# fpga-bank3.net
KiCad netlist of a schematic drawn in Altium Designer
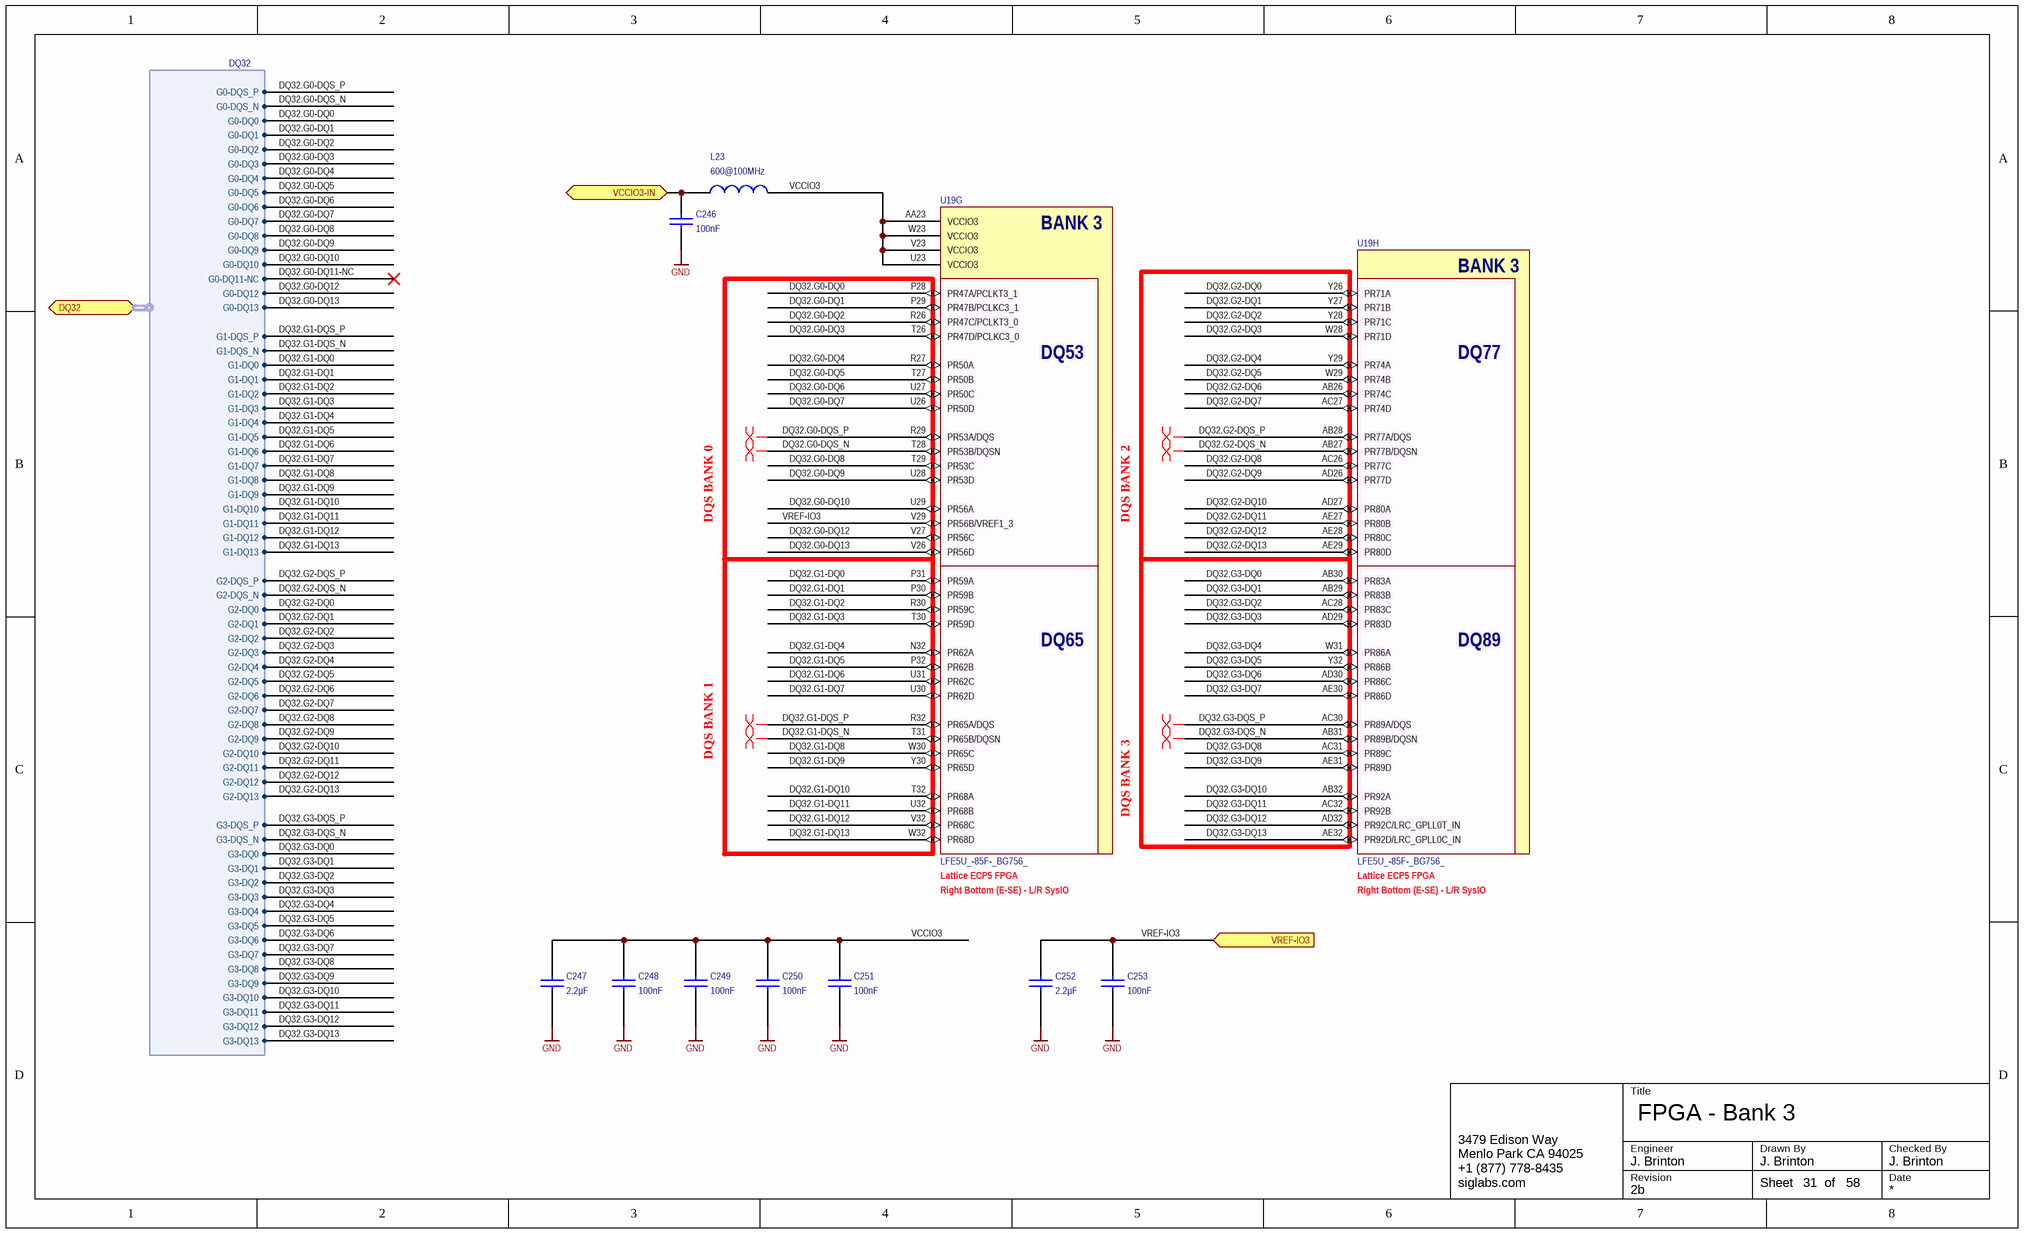
[diagram p0: fpga-bank3.SchDoc]

(export (version "E")
  (design (tool "Eeschema 10.0.6"))
  (components
    (comp (ref "C246")
      (value "100nF")
      (footprint "generic:CAPC1005X56N")
      (description "Ceramic Capacitor 100nF ±10% 16V X7R 0402")
      (fields (field (name "MANUFACTURER") "Murata") (field (name "TOLERANCE") "±10%"))
      (libsource (lib "murata") (part "GRM155R71A104KA01J"))
    )
    (comp (ref "C247")
      (value "2.2µF")
      (footprint "generic:CAPC1608X90N")
      (description "Ceramic Capacitor 2.2uF ±10% 10V X7R 0603")
      (fields (field (name "MANUFACTURER") "Murata") (field (name "TOLERANCE") "±10%"))
      (libsource (lib "murata") (part "GRM188R71A225KE15D"))
    )
    (comp (ref "C248")
      (value "100nF")
      (footprint "generic:CAPC1005X56N")
      (description "Ceramic Capacitor 100nF ±10% 16V X7R 0402")
      (fields (field (name "MANUFACTURER") "Murata") (field (name "TOLERANCE") "±10%"))
      (libsource (lib "murata") (part "GRM155R71A104KA01J"))
    )
    (comp (ref "C249")
      (value "100nF")
      (footprint "generic:CAPC1005X56N")
      (description "Ceramic Capacitor 100nF ±10% 16V X7R 0402")
      (fields (field (name "MANUFACTURER") "Murata") (field (name "TOLERANCE") "±10%"))
      (libsource (lib "murata") (part "GRM155R71A104KA01J"))
    )
    (comp (ref "C250")
      (value "100nF")
      (footprint "generic:CAPC1005X56N")
      (description "Ceramic Capacitor 100nF ±10% 16V X7R 0402")
      (fields (field (name "MANUFACTURER") "Murata") (field (name "TOLERANCE") "±10%"))
      (libsource (lib "murata") (part "GRM155R71A104KA01J"))
    )
    (comp (ref "C251")
      (value "100nF")
      (footprint "generic:CAPC1005X56N")
      (description "Ceramic Capacitor 100nF ±10% 16V X7R 0402")
      (fields (field (name "MANUFACTURER") "Murata") (field (name "TOLERANCE") "±10%"))
      (libsource (lib "murata") (part "GRM155R71A104KA01J"))
    )
    (comp (ref "C252")
      (value "2.2µF")
      (footprint "generic:CAPC1608X90N")
      (description "Ceramic Capacitor 2.2uF ±10% 10V X7R 0603")
      (fields (field (name "MANUFACTURER") "Murata") (field (name "TOLERANCE") "±10%"))
      (libsource (lib "murata") (part "GRM188R71A225KE15D"))
    )
    (comp (ref "C253")
      (value "100nF")
      (footprint "generic:CAPC1005X56N")
      (description "Ceramic Capacitor 100nF ±10% 16V X7R 0402")
      (fields (field (name "MANUFACTURER") "Murata") (field (name "TOLERANCE") "±10%"))
      (libsource (lib "murata") (part "GRM155R71A104KA01J"))
    )
    (comp (ref "L23")
      (value "600@100MHz")
      (footprint "0402")
      (description "Ferrite Bead 600-Ohm @ 100MHz 900mA 0402")
      (fields (field (name "MANUFACTURER") "Murata") (field (name "TOLERANCE") "±25%"))
      (libsource (lib "Graviton") (part "IND 0402"))
    )
    (comp (ref "U19")
      (value "LFE5U_-85F-_BG756_")
      (footprint "lattice:caBGA756")
      (description "ECP5 FPGA, 85k LUT, 756-caBGA")
      (fields (field (name "MANUFACTURER") "Lattice Semiconductor"))
      (libsource (lib "lattice") (part "LFE5U_-85F-_BG756_"))
    )
  )
  (nets
    (net (code "2") (name "/DQ32.G0-DQ0") (class "Default")
      (node (ref "U19") (pin "P28") (pinfunction "PR47A/PCLKT3_1_P28") (pintype "bidirectional"))
    )
    (net (code "3") (name "/DQ32.G0-DQ1") (class "Default")
      (node (ref "U19") (pin "P29") (pinfunction "PR47B/PCLKC3_1_P29") (pintype "bidirectional"))
    )
    (net (code "4") (name "/DQ32.G0-DQ2") (class "Default")
      (node (ref "U19") (pin "R26") (pinfunction "PR47C/PCLKT3_0_R26") (pintype "bidirectional"))
    )
    (net (code "5") (name "/DQ32.G0-DQ3") (class "Default")
      (node (ref "U19") (pin "T26") (pinfunction "PR47D/PCLKC3_0_T26") (pintype "bidirectional"))
    )
    (net (code "6") (name "/DQ32.G0-DQ4") (class "Default")
      (node (ref "U19") (pin "R27") (pinfunction "PR50A_R27") (pintype "bidirectional"))
    )
    (net (code "7") (name "/DQ32.G0-DQ5") (class "Default")
      (node (ref "U19") (pin "T27") (pinfunction "PR50B_T27") (pintype "bidirectional"))
    )
    (net (code "8") (name "/DQ32.G0-DQ6") (class "Default")
      (node (ref "U19") (pin "U27") (pinfunction "PR50C_U27") (pintype "bidirectional"))
    )
    (net (code "9") (name "/DQ32.G0-DQ7") (class "Default")
      (node (ref "U19") (pin "U26") (pinfunction "PR50D_U26") (pintype "bidirectional"))
    )
    (net (code "10") (name "/DQ32.G0-DQ8") (class "Default")
      (node (ref "U19") (pin "T29") (pinfunction "PR53C_T29") (pintype "bidirectional"))
    )
    (net (code "11") (name "/DQ32.G0-DQ9") (class "Default")
      (node (ref "U19") (pin "U28") (pinfunction "PR53D_U28") (pintype "bidirectional"))
    )
    (net (code "12") (name "/DQ32.G0-DQ10") (class "Default")
      (node (ref "U19") (pin "U29") (pinfunction "PR56A_U29") (pintype "bidirectional"))
    )
    (net (code "14") (name "/DQ32.G0-DQ12") (class "Default")
      (node (ref "U19") (pin "V27") (pinfunction "PR56C_V27") (pintype "bidirectional"))
    )
    (net (code "15") (name "/DQ32.G0-DQ13") (class "Default")
      (node (ref "U19") (pin "V26") (pinfunction "PR56D_V26") (pintype "bidirectional"))
    )
    (net (code "16") (name "/DQ32.G0-DQS_N") (class "Default")
      (node (ref "U19") (pin "T28") (pinfunction "PR53B/DQSN_T28") (pintype "bidirectional"))
    )
    (net (code "17") (name "/DQ32.G0-DQS_P") (class "Default")
      (node (ref "U19") (pin "R29") (pinfunction "PR53A/DQS_R29") (pintype "bidirectional"))
    )
    (net (code "18") (name "/DQ32.G1-DQ0") (class "Default")
      (node (ref "U19") (pin "P31") (pinfunction "PR59A_P31") (pintype "bidirectional"))
    )
    (net (code "19") (name "/DQ32.G1-DQ1") (class "Default")
      (node (ref "U19") (pin "P30") (pinfunction "PR59B_P30") (pintype "bidirectional"))
    )
    (net (code "20") (name "/DQ32.G1-DQ2") (class "Default")
      (node (ref "U19") (pin "R30") (pinfunction "PR59C_R30") (pintype "bidirectional"))
    )
    (net (code "21") (name "/DQ32.G1-DQ3") (class "Default")
      (node (ref "U19") (pin "T30") (pinfunction "PR59D_T30") (pintype "bidirectional"))
    )
    (net (code "22") (name "/DQ32.G1-DQ4") (class "Default")
      (node (ref "U19") (pin "N32") (pinfunction "PR62A_N32") (pintype "bidirectional"))
    )
    (net (code "23") (name "/DQ32.G1-DQ5") (class "Default")
      (node (ref "U19") (pin "P32") (pinfunction "PR62B_P32") (pintype "bidirectional"))
    )
    (net (code "24") (name "/DQ32.G1-DQ6") (class "Default")
      (node (ref "U19") (pin "U31") (pinfunction "PR62C_U31") (pintype "bidirectional"))
    )
    (net (code "25") (name "/DQ32.G1-DQ7") (class "Default")
      (node (ref "U19") (pin "U30") (pinfunction "PR62D_U30") (pintype "bidirectional"))
    )
    (net (code "26") (name "/DQ32.G1-DQ8") (class "Default")
      (node (ref "U19") (pin "W30") (pinfunction "PR65C_W30") (pintype "bidirectional"))
    )
    (net (code "27") (name "/DQ32.G1-DQ9") (class "Default")
      (node (ref "U19") (pin "Y30") (pinfunction "PR65D_Y30") (pintype "bidirectional"))
    )
    (net (code "28") (name "/DQ32.G1-DQ10") (class "Default")
      (node (ref "U19") (pin "T32") (pinfunction "PR68A_T32") (pintype "bidirectional"))
    )
    (net (code "29") (name "/DQ32.G1-DQ11") (class "Default")
      (node (ref "U19") (pin "U32") (pinfunction "PR68B_U32") (pintype "bidirectional"))
    )
    (net (code "30") (name "/DQ32.G1-DQ12") (class "Default")
      (node (ref "U19") (pin "V32") (pinfunction "PR68C_V32") (pintype "bidirectional"))
    )
    (net (code "31") (name "/DQ32.G1-DQ13") (class "Default")
      (node (ref "U19") (pin "W32") (pinfunction "PR68D_W32") (pintype "bidirectional"))
    )
    (net (code "32") (name "/DQ32.G1-DQS_N") (class "Default")
      (node (ref "U19") (pin "T31") (pinfunction "PR65B/DQSN_T31") (pintype "bidirectional"))
    )
    (net (code "33") (name "/DQ32.G1-DQS_P") (class "Default")
      (node (ref "U19") (pin "R32") (pinfunction "PR65A/DQS_R32") (pintype "bidirectional"))
    )
    (net (code "34") (name "/DQ32.G2-DQ0") (class "Default")
      (node (ref "U19") (pin "Y26") (pinfunction "PR71A_Y26") (pintype "bidirectional"))
    )
    (net (code "35") (name "/DQ32.G2-DQ1") (class "Default")
      (node (ref "U19") (pin "Y27") (pinfunction "PR71B_Y27") (pintype "bidirectional"))
    )
    (net (code "36") (name "/DQ32.G2-DQ2") (class "Default")
      (node (ref "U19") (pin "Y28") (pinfunction "PR71C_Y28") (pintype "bidirectional"))
    )
    (net (code "37") (name "/DQ32.G2-DQ3") (class "Default")
      (node (ref "U19") (pin "W28") (pinfunction "PR71D_W28") (pintype "bidirectional"))
    )
    (net (code "38") (name "/DQ32.G2-DQ4") (class "Default")
      (node (ref "U19") (pin "Y29") (pinfunction "PR74A_Y29") (pintype "bidirectional"))
    )
    (net (code "39") (name "/DQ32.G2-DQ5") (class "Default")
      (node (ref "U19") (pin "W29") (pinfunction "PR74B_W29") (pintype "bidirectional"))
    )
    (net (code "40") (name "/DQ32.G2-DQ6") (class "Default")
      (node (ref "U19") (pin "AB26") (pinfunction "PR74C_AB26") (pintype "bidirectional"))
    )
    (net (code "41") (name "/DQ32.G2-DQ7") (class "Default")
      (node (ref "U19") (pin "AC27") (pinfunction "PR74D_AC27") (pintype "bidirectional"))
    )
    (net (code "42") (name "/DQ32.G2-DQ8") (class "Default")
      (node (ref "U19") (pin "AC26") (pinfunction "PR77C_AC26") (pintype "bidirectional"))
    )
    (net (code "43") (name "/DQ32.G2-DQ9") (class "Default")
      (node (ref "U19") (pin "AD26") (pinfunction "PR77D_AD26") (pintype "bidirectional"))
    )
    (net (code "44") (name "/DQ32.G2-DQ10") (class "Default")
      (node (ref "U19") (pin "AD27") (pinfunction "PR80A_AD27") (pintype "bidirectional"))
    )
    (net (code "45") (name "/DQ32.G2-DQ11") (class "Default")
      (node (ref "U19") (pin "AE27") (pinfunction "PR80B_AE27") (pintype "bidirectional"))
    )
    (net (code "46") (name "/DQ32.G2-DQ12") (class "Default")
      (node (ref "U19") (pin "AE28") (pinfunction "PR80C_AE28") (pintype "bidirectional"))
    )
    (net (code "47") (name "/DQ32.G2-DQ13") (class "Default")
      (node (ref "U19") (pin "AE29") (pinfunction "PR80D_AE29") (pintype "bidirectional"))
    )
    (net (code "48") (name "/DQ32.G2-DQS_N") (class "Default")
      (node (ref "U19") (pin "AB27") (pinfunction "PR77B/DQSN_AB27") (pintype "bidirectional"))
    )
    (net (code "49") (name "/DQ32.G2-DQS_P") (class "Default")
      (node (ref "U19") (pin "AB28") (pinfunction "PR77A/DQS_AB28") (pintype "bidirectional"))
    )
    (net (code "50") (name "/DQ32.G3-DQ0") (class "Default")
      (node (ref "U19") (pin "AB30") (pinfunction "PR83A_AB30") (pintype "bidirectional"))
    )
    (net (code "51") (name "/DQ32.G3-DQ1") (class "Default")
      (node (ref "U19") (pin "AB29") (pinfunction "PR83B_AB29") (pintype "bidirectional"))
    )
    (net (code "52") (name "/DQ32.G3-DQ2") (class "Default")
      (node (ref "U19") (pin "AC28") (pinfunction "PR83C_AC28") (pintype "bidirectional"))
    )
    (net (code "53") (name "/DQ32.G3-DQ3") (class "Default")
      (node (ref "U19") (pin "AD29") (pinfunction "PR83D_AD29") (pintype "bidirectional"))
    )
    (net (code "54") (name "/DQ32.G3-DQ4") (class "Default")
      (node (ref "U19") (pin "W31") (pinfunction "PR86A_W31") (pintype "bidirectional"))
    )
    (net (code "55") (name "/DQ32.G3-DQ5") (class "Default")
      (node (ref "U19") (pin "Y32") (pinfunction "PR86B_Y32") (pintype "bidirectional"))
    )
    (net (code "56") (name "/DQ32.G3-DQ6") (class "Default")
      (node (ref "U19") (pin "AD30") (pinfunction "PR86C_AD30") (pintype "bidirectional"))
    )
    (net (code "57") (name "/DQ32.G3-DQ7") (class "Default")
      (node (ref "U19") (pin "AE30") (pinfunction "PR86D_AE30") (pintype "bidirectional"))
    )
    (net (code "58") (name "/DQ32.G3-DQ8") (class "Default")
      (node (ref "U19") (pin "AC31") (pinfunction "PR89C_AC31") (pintype "bidirectional"))
    )
    (net (code "59") (name "/DQ32.G3-DQ9") (class "Default")
      (node (ref "U19") (pin "AE31") (pinfunction "PR89D_AE31") (pintype "bidirectional"))
    )
    (net (code "60") (name "/DQ32.G3-DQ10") (class "Default")
      (node (ref "U19") (pin "AB32") (pinfunction "PR92A_AB32") (pintype "bidirectional"))
    )
    (net (code "61") (name "/DQ32.G3-DQ11") (class "Default")
      (node (ref "U19") (pin "AC32") (pinfunction "PR92B_AC32") (pintype "bidirectional"))
    )
    (net (code "62") (name "/DQ32.G3-DQ12") (class "Default")
      (node (ref "U19") (pin "AD32") (pinfunction "PR92C/LRC_GPLL0T_IN_AD32") (pintype "bidirectional"))
    )
    (net (code "63") (name "/DQ32.G3-DQ13") (class "Default")
      (node (ref "U19") (pin "AE32") (pinfunction "PR92D/LRC_GPLL0C_IN_AE32") (pintype "bidirectional"))
    )
    (net (code "64") (name "/DQ32.G3-DQS_N") (class "Default")
      (node (ref "U19") (pin "AB31") (pinfunction "PR89B/DQSN_AB31") (pintype "bidirectional"))
    )
    (net (code "65") (name "/DQ32.G3-DQS_P") (class "Default")
      (node (ref "U19") (pin "AC30") (pinfunction "PR89A/DQS_AC30") (pintype "bidirectional"))
    )
    (net (code "66") (name "/VCCIO3") (class "Default")
      (node (ref "C247") (pin "2") (pinfunction "2_2") (pintype "passive"))
      (node (ref "C248") (pin "2") (pinfunction "2_2") (pintype "passive"))
      (node (ref "C249") (pin "2") (pinfunction "2_2") (pintype "passive"))
      (node (ref "C250") (pin "2") (pinfunction "2_2") (pintype "passive"))
      (node (ref "C251") (pin "2") (pinfunction "2_2") (pintype "passive"))
      (node (ref "L23") (pin "1") (pinfunction "1_1") (pintype "passive"))
      (node (ref "U19") (pin "AA23") (pinfunction "VCCIO3_AA23") (pintype "power_in"))
      (node (ref "U19") (pin "U23") (pinfunction "VCCIO3_U23") (pintype "power_in"))
      (node (ref "U19") (pin "V23") (pinfunction "VCCIO3_V23") (pintype "power_in"))
      (node (ref "U19") (pin "W23") (pinfunction "VCCIO3_W23") (pintype "power_in"))
    )
    (net (code "67") (name "/VCCIO3-IN") (class "Default")
      (node (ref "C246") (pin "2") (pinfunction "2_2") (pintype "passive"))
      (node (ref "L23") (pin "2") (pinfunction "2_2") (pintype "passive"))
    )
    (net (code "68") (name "/VREF-IO3") (class "Default")
      (node (ref "C252") (pin "2") (pinfunction "2_2") (pintype "passive"))
      (node (ref "C253") (pin "2") (pinfunction "2_2") (pintype "passive"))
      (node (ref "U19") (pin "V29") (pinfunction "PR56B/VREF1_3_V29") (pintype "bidirectional"))
    )
    (net (code "70") (name "GND") (class "Default")
      (node (ref "C246") (pin "1") (pinfunction "1_1") (pintype "passive"))
      (node (ref "C247") (pin "1") (pinfunction "1_1") (pintype "passive"))
      (node (ref "C248") (pin "1") (pinfunction "1_1") (pintype "passive"))
      (node (ref "C249") (pin "1") (pinfunction "1_1") (pintype "passive"))
      (node (ref "C250") (pin "1") (pinfunction "1_1") (pintype "passive"))
      (node (ref "C251") (pin "1") (pinfunction "1_1") (pintype "passive"))
      (node (ref "C252") (pin "1") (pinfunction "1_1") (pintype "passive"))
      (node (ref "C253") (pin "1") (pinfunction "1_1") (pintype "passive"))
    )
  )
)
